# Teensylu-0_9.net
KiCad netlist of a schematic drawn in EAGLE
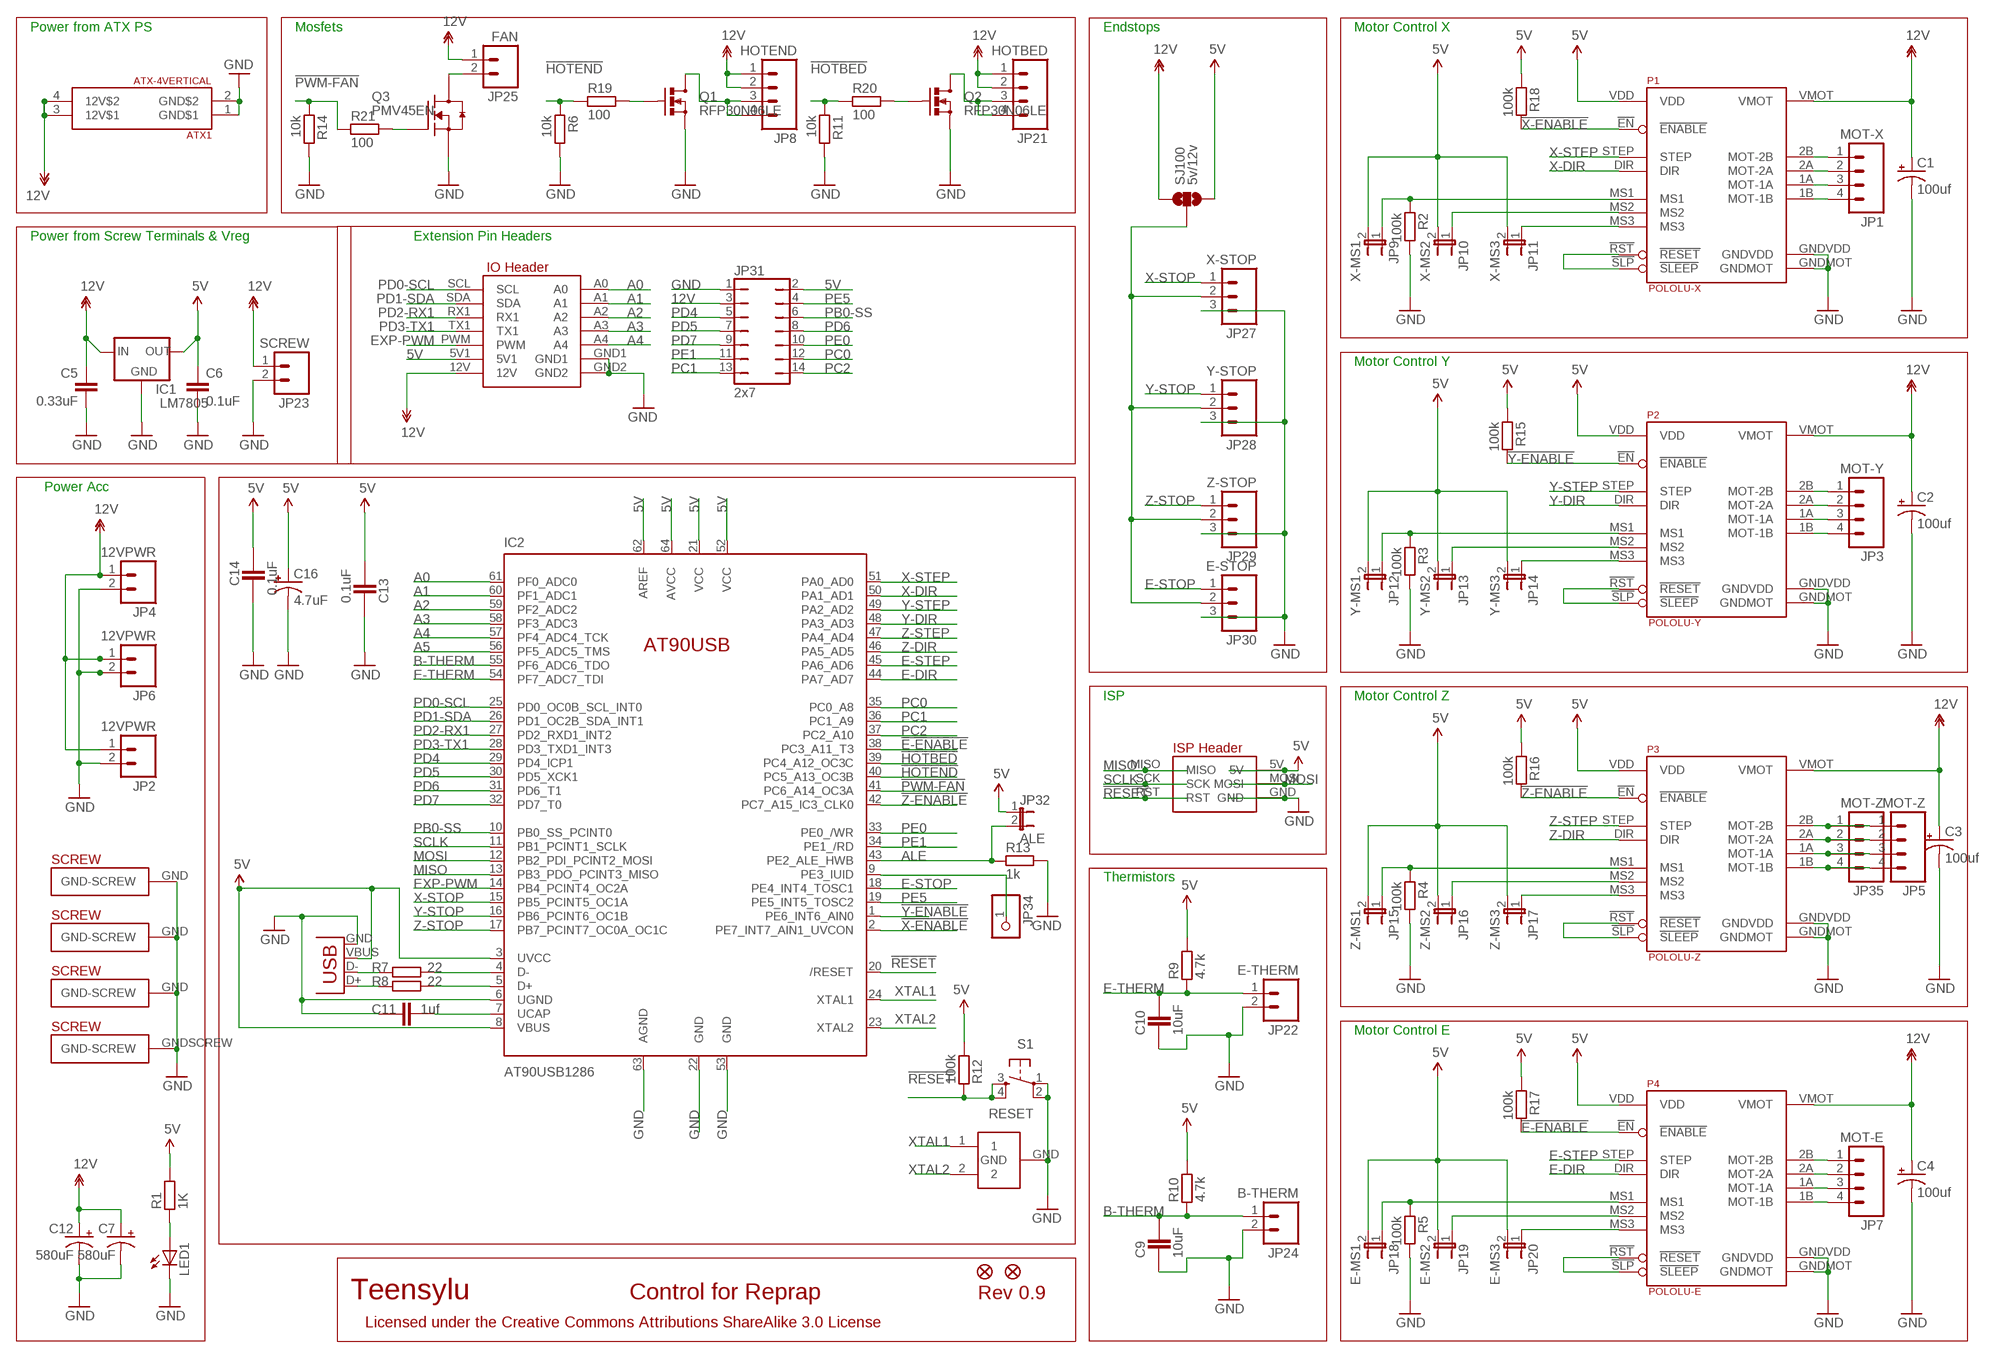
[diagram p0: schematic, sheet 1]

(export (version "E")
  (design (tool "Eeschema 10.0.6"))
  (components
    (comp (ref "ATX1")
      (value "ATX-4VERTICAL")
      (footprint "eagle-import:MINIFITJR-4-VERTICAL")
      (libsource (lib "eagle-import") (part "ATX-4VERTICAL"))
    )
    (comp (ref "C1")
      (value "100uf")
      (footprint "eagle-import:CPOL-RADIAL-100UF-25V")
      (libsource (lib "eagle-import") (part "CAP_POLPTH1"))
    )
    (comp (ref "C2")
      (value "100uf")
      (footprint "eagle-import:CPOL-RADIAL-100UF-25V")
      (libsource (lib "eagle-import") (part "CAP_POLPTH1"))
    )
    (comp (ref "C3")
      (value "100uf")
      (footprint "eagle-import:CPOL-RADIAL-100UF-25V")
      (libsource (lib "eagle-import") (part "CAP_POLPTH1"))
    )
    (comp (ref "C4")
      (value "100uf")
      (footprint "eagle-import:CPOL-RADIAL-100UF-25V")
      (libsource (lib "eagle-import") (part "CAP_POLPTH1"))
    )
    (comp (ref "C5")
      (value "0.33uF")
      (footprint "eagle-import:CAP-PTH-SMALL2")
      (libsource (lib "eagle-import") (part "CAPPTH2"))
    )
    (comp (ref "C6")
      (value "0.1uF")
      (footprint "eagle-import:CAP-PTH-SMALL2")
      (libsource (lib "eagle-import") (part "CAPPTH2"))
    )
    (comp (ref "C7")
      (value "580uF")
      (footprint "eagle-import:CPOL-RADIAL-1000UF-25V")
      (libsource (lib "eagle-import") (part "CAP_POLPTH4"))
    )
    (comp (ref "C9")
      (value "10uF")
      (footprint "eagle-import:CAPC1608X92N")
      (libsource (lib "eagle-import") (part "CAPACITOR_0603"))
    )
    (comp (ref "C10")
      (value "10uF")
      (footprint "eagle-import:CAPC1608X92N")
      (libsource (lib "eagle-import") (part "CAPACITOR_0603"))
    )
    (comp (ref "C11")
      (value "1uf")
      (footprint "eagle-import:CAPC1608X92N")
      (libsource (lib "eagle-import") (part "CAPACITOR_0603"))
    )
    (comp (ref "C12")
      (value "580uF")
      (footprint "eagle-import:CPOL-RADIAL-1000UF-25V")
      (libsource (lib "eagle-import") (part "CAP_POLPTH4"))
    )
    (comp (ref "C13")
      (value "0.1uF")
      (footprint "eagle-import:CAPC1608X92N")
      (libsource (lib "eagle-import") (part "CAPACITOR_0603"))
    )
    (comp (ref "C14")
      (value "0.1uF")
      (footprint "eagle-import:CAPC1608X92N")
      (libsource (lib "eagle-import") (part "CAPACITOR_0603"))
    )
    (comp (ref "C16")
      (value "4.7uF")
      (footprint "eagle-import:CPOL-RADIAL-10UF-25V")
      (libsource (lib "eagle-import") (part "CAP_POLPTH2"))
    )
    (comp (ref "IC1")
      (value "LM7805")
      (footprint "eagle-import:78XXL-CUSTOM")
      (libsource (lib "eagle-import") (part "V_REG_78XX"))
    )
    (comp (ref "IC2")
      (value "AT90USB1286")
      (footprint "eagle-import:TQFP64-2")
      (libsource (lib "eagle-import") (part "AT90USB"))
    )
    (comp (ref "J1")
      (value "USB")
      (footprint "eagle-import:USB-B-PTH")
      (libsource (lib "eagle-import") (part "USBPTH"))
    )
    (comp (ref "JP1")
      (value "MOT-X")
      (footprint "eagle-import:MOLEX-1X4")
      (libsource (lib "eagle-import") (part "M04POLAR"))
    )
    (comp (ref "JP2")
      (value "12VPWR")
      (footprint "eagle-import:MOLEX-1X2")
      (libsource (lib "eagle-import") (part "M02POLAR"))
    )
    (comp (ref "JP3")
      (value "MOT-Y")
      (footprint "eagle-import:MOLEX-1X4")
      (libsource (lib "eagle-import") (part "M04POLAR"))
    )
    (comp (ref "JP4")
      (value "12VPWR")
      (footprint "eagle-import:MOLEX-1X2")
      (libsource (lib "eagle-import") (part "M02POLAR"))
    )
    (comp (ref "JP5")
      (value "MOT-Z")
      (footprint "eagle-import:MOLEX-1X4")
      (libsource (lib "eagle-import") (part "M04POLAR"))
    )
    (comp (ref "JP6")
      (value "12VPWR")
      (footprint "eagle-import:MOLEX-1X2")
      (libsource (lib "eagle-import") (part "M02POLAR"))
    )
    (comp (ref "JP7")
      (value "MOT-E")
      (footprint "eagle-import:MOLEX-1X4")
      (libsource (lib "eagle-import") (part "M04POLAR"))
    )
    (comp (ref "JP8")
      (value "HOTEND")
      (footprint "eagle-import:MOLEX-1X4")
      (libsource (lib "eagle-import") (part "M04POLAR"))
    )
    (comp (ref "JP9")
      (value "X-MS1")
      (footprint "eagle-import:1X02")
      (libsource (lib "eagle-import") (part "JUMPER-2PTH"))
    )
    (comp (ref "JP10")
      (value "X-MS2")
      (footprint "eagle-import:1X02")
      (libsource (lib "eagle-import") (part "JUMPER-2PTH"))
    )
    (comp (ref "JP11")
      (value "X-MS3")
      (footprint "eagle-import:1X02")
      (libsource (lib "eagle-import") (part "JUMPER-2PTH"))
    )
    (comp (ref "JP12")
      (value "Y-MS1")
      (footprint "eagle-import:1X02")
      (libsource (lib "eagle-import") (part "JUMPER-2PTH"))
    )
    (comp (ref "JP13")
      (value "Y-MS2")
      (footprint "eagle-import:1X02")
      (libsource (lib "eagle-import") (part "JUMPER-2PTH"))
    )
    (comp (ref "JP14")
      (value "Y-MS3")
      (footprint "eagle-import:1X02")
      (libsource (lib "eagle-import") (part "JUMPER-2PTH"))
    )
    (comp (ref "JP15")
      (value "Z-MS1")
      (footprint "eagle-import:1X02")
      (libsource (lib "eagle-import") (part "JUMPER-2PTH"))
    )
    (comp (ref "JP16")
      (value "Z-MS2")
      (footprint "eagle-import:1X02")
      (libsource (lib "eagle-import") (part "JUMPER-2PTH"))
    )
    (comp (ref "JP17")
      (value "Z-MS3")
      (footprint "eagle-import:1X02")
      (libsource (lib "eagle-import") (part "JUMPER-2PTH"))
    )
    (comp (ref "JP18")
      (value "E-MS1")
      (footprint "eagle-import:1X02")
      (libsource (lib "eagle-import") (part "JUMPER-2PTH"))
    )
    (comp (ref "JP19")
      (value "E-MS2")
      (footprint "eagle-import:1X02")
      (libsource (lib "eagle-import") (part "JUMPER-2PTH"))
    )
    (comp (ref "JP20")
      (value "E-MS3")
      (footprint "eagle-import:1X02")
      (libsource (lib "eagle-import") (part "JUMPER-2PTH"))
    )
    (comp (ref "JP21")
      (value "HOTBED")
      (footprint "eagle-import:MOLEX-1X4")
      (libsource (lib "eagle-import") (part "M04POLAR"))
    )
    (comp (ref "JP22")
      (value "E-THERM")
      (footprint "eagle-import:1X02")
      (libsource (lib "eagle-import") (part "M02PTH"))
    )
    (comp (ref "JP23")
      (value "SCREW")
      (footprint "eagle-import:SCREWTERMINAL-5MM-2")
      (libsource (lib "eagle-import") (part "M025MM"))
    )
    (comp (ref "JP24")
      (value "B-THERM")
      (footprint "eagle-import:1X02")
      (libsource (lib "eagle-import") (part "M02PTH"))
    )
    (comp (ref "JP25")
      (value "FAN")
      (footprint "eagle-import:1X02")
      (libsource (lib "eagle-import") (part "M02PTH"))
    )
    (comp (ref "JP26")
      (value "FIDUCIAL1X2.5")
      (footprint "eagle-import:FIDUCIAL-1X2.5")
      (libsource (lib "eagle-import") (part "FIDUCIAL1X2.5"))
    )
    (comp (ref "JP27")
      (value "X-STOP")
      (footprint "eagle-import:MOLEX-1X3")
      (libsource (lib "eagle-import") (part "M03POLAR"))
    )
    (comp (ref "JP28")
      (value "Y-STOP")
      (footprint "eagle-import:MOLEX-1X3")
      (libsource (lib "eagle-import") (part "M03POLAR"))
    )
    (comp (ref "JP29")
      (value "Z-STOP")
      (footprint "eagle-import:MOLEX-1X3")
      (libsource (lib "eagle-import") (part "M03POLAR"))
    )
    (comp (ref "JP30")
      (value "E-STOP")
      (footprint "eagle-import:MOLEX-1X3")
      (libsource (lib "eagle-import") (part "M03POLAR"))
    )
    (comp (ref "JP31")
      (value "2x7")
      (footprint "eagle-import:JP7Q")
      (libsource (lib "eagle-import") (part "JP7Q"))
    )
    (comp (ref "JP32")
      (value "ALE")
      (footprint "eagle-import:1X02")
      (libsource (lib "eagle-import") (part "JUMPER-2PTH"))
    )
    (comp (ref "JP33")
      (value "FIDUCIAL1X2.5")
      (footprint "eagle-import:FIDUCIAL-1X2.5")
      (libsource (lib "eagle-import") (part "FIDUCIAL1X2.5"))
    )
    (comp (ref "JP34")
      (value "PINHD-1X1")
      (footprint "eagle-import:1X01")
      (libsource (lib "eagle-import") (part "PINHD-1X1"))
    )
    (comp (ref "JP35")
      (value "MOT-Z")
      (footprint "eagle-import:MOLEX-1X4")
      (libsource (lib "eagle-import") (part "M04POLAR"))
    )
    (comp (ref "LED1")
      (value "LED5MM")
      (footprint "eagle-import:LED5MM")
      (libsource (lib "eagle-import") (part "LED5MM"))
    )
    (comp (ref "P1")
      (value "POLOLU-X")
      (footprint "eagle-import:POLOLU-ALLEGRO-PTH")
      (libsource (lib "eagle-import") (part "POLOLU-ALLEGRO"))
    )
    (comp (ref "P2")
      (value "POLOLU-Y")
      (footprint "eagle-import:POLOLU-ALLEGRO-PTH")
      (libsource (lib "eagle-import") (part "POLOLU-ALLEGRO"))
    )
    (comp (ref "P3")
      (value "POLOLU-Z")
      (footprint "eagle-import:POLOLU-ALLEGRO-PTH")
      (libsource (lib "eagle-import") (part "POLOLU-ALLEGRO"))
    )
    (comp (ref "P4")
      (value "POLOLU-E")
      (footprint "eagle-import:POLOLU-ALLEGRO-PTH")
      (libsource (lib "eagle-import") (part "POLOLU-ALLEGRO"))
    )
    (comp (ref "Q1")
      (value "RFP30N06LE")
      (footprint "eagle-import:TO220V")
      (libsource (lib "eagle-import") (part "MOSFET-NCHANNELPTH2"))
    )
    (comp (ref "Q2")
      (value "RFP30N06LE")
      (footprint "eagle-import:TO220V")
      (libsource (lib "eagle-import") (part "MOSFET-NCHANNELPTH2"))
    )
    (comp (ref "Q3")
      (value "PMV45EN")
      (footprint "eagle-import:SOT95P280X135-3N")
      (libsource (lib "eagle-import") (part "MOSFET-NCH_SOT-23"))
    )
    (comp (ref "R1")
      (value "1K")
      (footprint "eagle-import:RESC1608X55N")
      (libsource (lib "eagle-import") (part "RESISTOR_0603"))
    )
    (comp (ref "R2")
      (value "100k")
      (footprint "eagle-import:RESC1608X55N")
      (libsource (lib "eagle-import") (part "RESISTOR_0603"))
    )
    (comp (ref "R3")
      (value "100k")
      (footprint "eagle-import:RESC1608X55N")
      (libsource (lib "eagle-import") (part "RESISTOR_0603"))
    )
    (comp (ref "R4")
      (value "100k")
      (footprint "eagle-import:RESC1608X55N")
      (libsource (lib "eagle-import") (part "RESISTOR_0603"))
    )
    (comp (ref "R5")
      (value "100k")
      (footprint "eagle-import:RESC1608X55N")
      (libsource (lib "eagle-import") (part "RESISTOR_0603"))
    )
    (comp (ref "R6")
      (value "10k")
      (footprint "eagle-import:RESC1608X55N")
      (libsource (lib "eagle-import") (part "RESISTOR_0603"))
    )
    (comp (ref "R7")
      (value "22")
      (footprint "eagle-import:RESC1608X55N")
      (libsource (lib "eagle-import") (part "RESISTOR_0603"))
    )
    (comp (ref "R8")
      (value "22")
      (footprint "eagle-import:RESC1608X55N")
      (libsource (lib "eagle-import") (part "RESISTOR_0603"))
    )
    (comp (ref "R9")
      (value "4.7k")
      (footprint "eagle-import:RESC1608X55N")
      (libsource (lib "eagle-import") (part "RESISTOR_0603"))
    )
    (comp (ref "R10")
      (value "4.7k")
      (footprint "eagle-import:RESC1608X55N")
      (libsource (lib "eagle-import") (part "RESISTOR_0603"))
    )
    (comp (ref "R11")
      (value "10k")
      (footprint "eagle-import:RESC1608X55N")
      (libsource (lib "eagle-import") (part "RESISTOR_0603"))
    )
    (comp (ref "R12")
      (value "100k")
      (footprint "eagle-import:RESC1608X55N")
      (libsource (lib "eagle-import") (part "RESISTOR_0603"))
    )
    (comp (ref "R13")
      (value "1k")
      (footprint "eagle-import:RESC1608X55N")
      (libsource (lib "eagle-import") (part "RESISTOR_0603"))
    )
    (comp (ref "R14")
      (value "10k")
      (footprint "eagle-import:RESC1608X55N")
      (libsource (lib "eagle-import") (part "RESISTOR_0603"))
    )
    (comp (ref "R15")
      (value "100k")
      (footprint "eagle-import:RESC1608X55N")
      (libsource (lib "eagle-import") (part "RESISTOR_0603"))
    )
    (comp (ref "R16")
      (value "100k")
      (footprint "eagle-import:RESC1608X55N")
      (libsource (lib "eagle-import") (part "RESISTOR_0603"))
    )
    (comp (ref "R17")
      (value "100k")
      (footprint "eagle-import:RESC1608X55N")
      (libsource (lib "eagle-import") (part "RESISTOR_0603"))
    )
    (comp (ref "R18")
      (value "100k")
      (footprint "eagle-import:RESC1608X55N")
      (libsource (lib "eagle-import") (part "RESISTOR_0603"))
    )
    (comp (ref "R19")
      (value "100")
      (footprint "eagle-import:RESC1608X55N")
      (libsource (lib "eagle-import") (part "RESISTOR_0603"))
    )
    (comp (ref "R20")
      (value "100")
      (footprint "eagle-import:RESC1608X55N")
      (libsource (lib "eagle-import") (part "RESISTOR_0603"))
    )
    (comp (ref "R21")
      (value "100")
      (footprint "eagle-import:RESC1608X55N")
      (libsource (lib "eagle-import") (part "RESISTOR_0603"))
    )
    (comp (ref "S1")
      (value "RESET")
      (footprint "eagle-import:TACTILE-PTH")
      (libsource (lib "eagle-import") (part "TAC_SWITCHPTH"))
    )
    (comp (ref "SJ100")
      (value "5v/12v")
      (footprint "eagle-import:SJ_2W")
      (libsource (lib "eagle-import") (part "SOLDERJUMPER_2WAYW"))
    )
    (comp (ref "U$17")
      (value "PLATED-SCREW")
      (footprint "eagle-import:PLATEDSCREW")
      (libsource (lib "eagle-import") (part "PLATED-SCREW"))
    )
    (comp (ref "U$24")
      (value "PLATED-SCREW")
      (footprint "eagle-import:PLATEDSCREW")
      (libsource (lib "eagle-import") (part "PLATED-SCREW"))
    )
    (comp (ref "U$34")
      (value "IO_HEADERS_SCREW")
      (footprint "eagle-import:IO_HEADER-PLATEDSCREW")
      (libsource (lib "eagle-import") (part "IO_HEADERS_SCREW"))
    )
    (comp (ref "U$37")
      (value "PLATED-SCREW")
      (footprint "eagle-import:PLATEDSCREW")
      (libsource (lib "eagle-import") (part "PLATED-SCREW"))
    )
    (comp (ref "XTAL")
      (value "KYOCERA_PQRC_TYPE_S_RESONATOR")
      (footprint "eagle-import:AVX_3.2X1.3_RESONATOR")
      (libsource (lib "eagle-import") (part "KYOCERA_PQRC_TYPE_S_RESONATOR"))
    )
  )
  (nets
    (net (code "1") (name "/A0") (class "Default")
      (node (ref "IC2") (pin "61") (pinfunction "PF0_ADC0_61") (pintype "bidirectional"))
      (node (ref "U$34") (pin "A0") (pinfunction "A0_A0") (pintype "bidirectional"))
    )
    (net (code "2") (name "/A1") (class "Default")
      (node (ref "IC2") (pin "60") (pinfunction "PF1_ADC1_60") (pintype "bidirectional"))
      (node (ref "U$34") (pin "A1") (pinfunction "A1_A1") (pintype "bidirectional"))
    )
    (net (code "3") (name "/A2") (class "Default")
      (node (ref "IC2") (pin "59") (pinfunction "PF2_ADC2_59") (pintype "bidirectional"))
      (node (ref "U$34") (pin "A2") (pinfunction "A2_A2") (pintype "bidirectional"))
    )
    (net (code "4") (name "/A3") (class "Default")
      (node (ref "IC2") (pin "58") (pinfunction "PF3_ADC3_58") (pintype "bidirectional"))
      (node (ref "U$34") (pin "A3") (pinfunction "A3_A3") (pintype "bidirectional"))
    )
    (net (code "5") (name "/A4") (class "Default")
      (node (ref "IC2") (pin "57") (pinfunction "PF4_ADC4_TCK_57") (pintype "bidirectional"))
      (node (ref "U$34") (pin "A4") (pinfunction "A4_A4") (pintype "bidirectional"))
    )
    (net (code "6") (name "/A5") (class "Default")
      (node (ref "IC2") (pin "56") (pinfunction "PF5_ADC5_TMS_56") (pintype "bidirectional"))
    )
    (net (code "7") (name "/ALE") (class "Default")
      (node (ref "IC2") (pin "43") (pinfunction "PE2_ALE_HWB_43") (pintype "bidirectional"))
      (node (ref "JP32") (pin "2") (pinfunction "2_2") (pintype "passive"))
      (node (ref "R13") (pin "1") (pinfunction "1_1") (pintype "passive"))
    )
    (net (code "8") (name "/B-THERM") (class "Default")
      (node (ref "C9") (pin "2") (pinfunction "2_2") (pintype "passive"))
      (node (ref "IC2") (pin "55") (pinfunction "PF6_ADC6_TDO_55") (pintype "bidirectional"))
      (node (ref "JP24") (pin "1") (pinfunction "1_1") (pintype "passive"))
      (node (ref "R10") (pin "1") (pinfunction "1_1") (pintype "passive"))
    )
    (net (code "9") (name "/E-DIR") (class "Default")
      (node (ref "IC2") (pin "44") (pinfunction "PA7_AD7_44") (pintype "bidirectional"))
      (node (ref "P4") (pin "DIR") (pinfunction "DIR_DIR") (pintype "bidirectional"))
    )
    (net (code "10") (name "/E-STEP") (class "Default")
      (node (ref "IC2") (pin "45") (pinfunction "PA6_AD6_45") (pintype "bidirectional"))
      (node (ref "P4") (pin "STEP") (pinfunction "STEP_STEP") (pintype "bidirectional"))
    )
    (net (code "11") (name "/E-STOP") (class "Default")
      (node (ref "IC2") (pin "18") (pinfunction "PE4_INT4_TOSC1_18") (pintype "bidirectional"))
      (node (ref "JP30") (pin "1") (pinfunction "1_1") (pintype "passive"))
    )
    (net (code "12") (name "/E-THERM") (class "Default")
      (node (ref "C10") (pin "2") (pinfunction "2_2") (pintype "passive"))
      (node (ref "IC2") (pin "54") (pinfunction "PF7_ADC7_TDI_54") (pintype "bidirectional"))
      (node (ref "JP22") (pin "1") (pinfunction "1_1") (pintype "passive"))
      (node (ref "R9") (pin "1") (pinfunction "1_1") (pintype "passive"))
    )
    (net (code "13") (name "/EXP-PWM") (class "Default")
      (node (ref "IC2") (pin "14") (pinfunction "PB4_PCINT4_OC2A_14") (pintype "bidirectional"))
      (node (ref "U$34") (pin "PWM") (pinfunction "PWM_PWM") (pintype "bidirectional"))
    )
    (net (code "14") (name "/MISO") (class "Default")
      (node (ref "IC2") (pin "13") (pinfunction "PB3_PDO_PCINT3_MISO_13") (pintype "bidirectional"))
      (node (ref "U$34") (pin "MISO") (pinfunction "MISO_MISO") (pintype "bidirectional"))
    )
    (net (code "15") (name "/MOSI") (class "Default")
      (node (ref "IC2") (pin "12") (pinfunction "PB2_PDI_PCINT2_MOSI_12") (pintype "bidirectional"))
      (node (ref "U$34") (pin "MOSI") (pinfunction "MOSI_MOSI") (pintype "bidirectional"))
    )
    (net (code "16") (name "/PB0-SS") (class "Default")
      (node (ref "IC2") (pin "10") (pinfunction "PB0_SS_PCINT0_10") (pintype "bidirectional"))
      (node (ref "JP31") (pin "6") (pinfunction "6_6") (pintype "passive"))
    )
    (net (code "17") (name "/PC0") (class "Default")
      (node (ref "IC2") (pin "35") (pinfunction "PC0_A8_35") (pintype "bidirectional"))
      (node (ref "JP31") (pin "12") (pinfunction "12_12") (pintype "passive"))
    )
    (net (code "18") (name "/PC1") (class "Default")
      (node (ref "IC2") (pin "36") (pinfunction "PC1_A9_36") (pintype "bidirectional"))
      (node (ref "JP31") (pin "13") (pinfunction "13_13") (pintype "passive"))
    )
    (net (code "19") (name "/PC2") (class "Default")
      (node (ref "IC2") (pin "37") (pinfunction "PC2_A10_37") (pintype "bidirectional"))
      (node (ref "JP31") (pin "14") (pinfunction "14_14") (pintype "passive"))
    )
    (net (code "20") (name "/PD0-SCL") (class "Default")
      (node (ref "IC2") (pin "25") (pinfunction "PD0_OC0B_SCL_INT0_25") (pintype "bidirectional"))
      (node (ref "U$34") (pin "SCL") (pinfunction "SCL_SCL") (pintype "bidirectional"))
    )
    (net (code "21") (name "/PD1-SDA") (class "Default")
      (node (ref "IC2") (pin "26") (pinfunction "PD1_OC2B_SDA_INT1_26") (pintype "bidirectional"))
      (node (ref "U$34") (pin "SDA") (pinfunction "SDA_SDA") (pintype "bidirectional"))
    )
    (net (code "22") (name "/PD2-RX1") (class "Default")
      (node (ref "IC2") (pin "27") (pinfunction "PD2_RXD1_INT2_27") (pintype "bidirectional"))
      (node (ref "U$34") (pin "RX1") (pinfunction "RX1_RX1") (pintype "bidirectional"))
    )
    (net (code "23") (name "/PD3-TX1") (class "Default")
      (node (ref "IC2") (pin "28") (pinfunction "PD3_TXD1_INT3_28") (pintype "bidirectional"))
      (node (ref "U$34") (pin "TX1") (pinfunction "TX1_TX1") (pintype "bidirectional"))
    )
    (net (code "24") (name "/PD4") (class "Default")
      (node (ref "IC2") (pin "29") (pinfunction "PD4_ICP1_29") (pintype "bidirectional"))
      (node (ref "JP31") (pin "5") (pinfunction "5_5") (pintype "passive"))
    )
    (net (code "25") (name "/PD5") (class "Default")
      (node (ref "IC2") (pin "30") (pinfunction "PD5_XCK1_30") (pintype "bidirectional"))
      (node (ref "JP31") (pin "7") (pinfunction "7_7") (pintype "passive"))
    )
    (net (code "26") (name "/PD6") (class "Default")
      (node (ref "IC2") (pin "31") (pinfunction "PD6_T1_31") (pintype "bidirectional"))
      (node (ref "JP31") (pin "8") (pinfunction "8_8") (pintype "passive"))
    )
    (net (code "27") (name "/PD7") (class "Default")
      (node (ref "IC2") (pin "32") (pinfunction "PD7_T0_32") (pintype "bidirectional"))
      (node (ref "JP31") (pin "9") (pinfunction "9_9") (pintype "passive"))
    )
    (net (code "28") (name "/PE0") (class "Default")
      (node (ref "IC2") (pin "33") (pinfunction "PE0_/WR_33") (pintype "bidirectional"))
      (node (ref "JP31") (pin "10") (pinfunction "10_10") (pintype "passive"))
    )
    (net (code "29") (name "/PE1") (class "Default")
      (node (ref "IC2") (pin "34") (pinfunction "PE1_/RD_34") (pintype "bidirectional"))
      (node (ref "JP31") (pin "11") (pinfunction "11_11") (pintype "passive"))
    )
    (net (code "30") (name "/PE5") (class "Default")
      (node (ref "IC2") (pin "19") (pinfunction "PE5_INT5_TOSC2_19") (pintype "bidirectional"))
      (node (ref "JP31") (pin "4") (pinfunction "4_4") (pintype "passive"))
    )
    (net (code "31") (name "/SCLK") (class "Default")
      (node (ref "IC2") (pin "11") (pinfunction "PB1_PCINT1_SCLK_11") (pintype "bidirectional"))
      (node (ref "U$34") (pin "SCK") (pinfunction "SCK_SCK") (pintype "bidirectional"))
    )
    (net (code "32") (name "/X-DIR") (class "Default")
      (node (ref "IC2") (pin "50") (pinfunction "PA1_AD1_50") (pintype "bidirectional"))
      (node (ref "P1") (pin "DIR") (pinfunction "DIR_DIR") (pintype "bidirectional"))
    )
    (net (code "33") (name "/X-STEP") (class "Default")
      (node (ref "IC2") (pin "51") (pinfunction "PA0_AD0_51") (pintype "bidirectional"))
      (node (ref "P1") (pin "STEP") (pinfunction "STEP_STEP") (pintype "bidirectional"))
    )
    (net (code "34") (name "/X-STOP") (class "Default")
      (node (ref "IC2") (pin "15") (pinfunction "PB5_PCINT5_OC1A_15") (pintype "bidirectional"))
      (node (ref "JP27") (pin "1") (pinfunction "1_1") (pintype "passive"))
    )
    (net (code "35") (name "/XTAL1") (class "Default")
      (node (ref "IC2") (pin "24") (pinfunction "XTAL1_24") (pintype "passive"))
      (node (ref "XTAL") (pin "1") (pinfunction "1_1") (pintype "bidirectional"))
    )
    (net (code "36") (name "/XTAL2") (class "Default")
      (node (ref "IC2") (pin "23") (pinfunction "XTAL2_23") (pintype "passive"))
      (node (ref "XTAL") (pin "2") (pinfunction "2_2") (pintype "bidirectional"))
    )
    (net (code "37") (name "/Y-DIR") (class "Default")
      (node (ref "IC2") (pin "48") (pinfunction "PA3_AD3_48") (pintype "bidirectional"))
      (node (ref "P2") (pin "DIR") (pinfunction "DIR_DIR") (pintype "bidirectional"))
    )
    (net (code "38") (name "/Y-STEP") (class "Default")
      (node (ref "IC2") (pin "49") (pinfunction "PA2_AD2_49") (pintype "bidirectional"))
      (node (ref "P2") (pin "STEP") (pinfunction "STEP_STEP") (pintype "bidirectional"))
    )
    (net (code "39") (name "/Y-STOP") (class "Default")
      (node (ref "IC2") (pin "16") (pinfunction "PB6_PCINT6_OC1B_16") (pintype "bidirectional"))
      (node (ref "JP28") (pin "1") (pinfunction "1_1") (pintype "passive"))
    )
    (net (code "40") (name "/Z-DIR") (class "Default")
      (node (ref "IC2") (pin "46") (pinfunction "PA5_AD5_46") (pintype "bidirectional"))
      (node (ref "P3") (pin "DIR") (pinfunction "DIR_DIR") (pintype "bidirectional"))
    )
    (net (code "41") (name "/Z-STEP") (class "Default")
      (node (ref "IC2") (pin "47") (pinfunction "PA4_AD4_47") (pintype "bidirectional"))
      (node (ref "P3") (pin "STEP") (pinfunction "STEP_STEP") (pintype "bidirectional"))
    )
    (net (code "42") (name "/Z-STOP") (class "Default")
      (node (ref "IC2") (pin "17") (pinfunction "PB7_PCINT7_OC0A_OC1C_17") (pintype "bidirectional"))
      (node (ref "JP29") (pin "1") (pinfunction "1_1") (pintype "passive"))
    )
    (net (code "43") (name "/~{E-ENABLE}") (class "Default")
      (node (ref "IC2") (pin "38") (pinfunction "PC3_A11_T3_38") (pintype "bidirectional"))
      (node (ref "P4") (pin "!EN") (pinfunction "~{ENABLE}_!EN") (pintype "input"))
      (node (ref "R17") (pin "2") (pinfunction "2_2") (pintype "passive"))
    )
    (net (code "44") (name "/~{HOTBED}") (class "Default")
      (node (ref "IC2") (pin "39") (pinfunction "PC4_A12_OC3C_39") (pintype "bidirectional"))
      (node (ref "R11") (pin "1") (pinfunction "1_1") (pintype "passive"))
      (node (ref "R20") (pin "1") (pinfunction "1_1") (pintype "passive"))
    )
    (net (code "45") (name "/~{HOTEND}") (class "Default")
      (node (ref "IC2") (pin "40") (pinfunction "PC5_A13_OC3B_40") (pintype "bidirectional"))
      (node (ref "R19") (pin "1") (pinfunction "1_1") (pintype "passive"))
      (node (ref "R6") (pin "1") (pinfunction "1_1") (pintype "passive"))
    )
    (net (code "46") (name "/~{PWM-FAN}") (class "Default")
      (node (ref "IC2") (pin "41") (pinfunction "PC6_A14_OC3A_41") (pintype "bidirectional"))
      (node (ref "R14") (pin "1") (pinfunction "1_1") (pintype "passive"))
      (node (ref "R21") (pin "1") (pinfunction "1_1") (pintype "passive"))
    )
    (net (code "47") (name "/~{RESET}") (class "Default")
      (node (ref "IC2") (pin "20") (pinfunction "/RESET_20") (pintype "bidirectional"))
      (node (ref "R12") (pin "1") (pinfunction "1_1") (pintype "passive"))
      (node (ref "S1") (pin "3") (pinfunction "3_3") (pintype "passive"))
      (node (ref "S1") (pin "4") (pinfunction "4_4") (pintype "passive"))
      (node (ref "U$34") (pin "RST") (pinfunction "RST_RST") (pintype "bidirectional"))
    )
    (net (code "48") (name "/~{X-ENABLE}") (class "Default")
      (node (ref "IC2") (pin "2") (pinfunction "PE7_INT7_AIN1_UVCON_2") (pintype "bidirectional"))
      (node (ref "P1") (pin "!EN") (pinfunction "~{ENABLE}_!EN") (pintype "input"))
      (node (ref "R18") (pin "2") (pinfunction "2_2") (pintype "passive"))
    )
    (net (code "49") (name "/~{Y-ENABLE}") (class "Default")
      (node (ref "IC2") (pin "1") (pinfunction "PE6_INT6_AIN0_1") (pintype "bidirectional"))
      (node (ref "P2") (pin "!EN") (pinfunction "~{ENABLE}_!EN") (pintype "input"))
      (node (ref "R15") (pin "2") (pinfunction "2_2") (pintype "passive"))
    )
    (net (code "50") (name "/~{Z-ENABLE}") (class "Default")
      (node (ref "IC2") (pin "42") (pinfunction "PC7_A15_IC3_CLK0_42") (pintype "bidirectional"))
      (node (ref "P3") (pin "!EN") (pinfunction "~{ENABLE}_!EN") (pintype "input"))
      (node (ref "R16") (pin "2") (pinfunction "2_2") (pintype "passive"))
    )
    (net (code "51") (name "5V") (class "Default")
      (node (ref "C13") (pin "2") (pinfunction "2_2") (pintype "passive"))
      (node (ref "C14") (pin "1") (pinfunction "1_1") (pintype "passive"))
      (node (ref "C16") (pin "1") (pinfunction "+_1") (pintype "passive"))
      (node (ref "C6") (pin "1") (pinfunction "1_1") (pintype "passive"))
      (node (ref "IC1") (pin "OUT") (pinfunction "OUT_OUT") (pintype "output"))
      (node (ref "IC2") (pin "21") (pinfunction "VCC_21") (pintype "power_in"))
      (node (ref "IC2") (pin "3") (pinfunction "UVCC_3") (pintype "power_in"))
      (node (ref "IC2") (pin "52") (pinfunction "VCC_52") (pintype "power_in"))
      (node (ref "IC2") (pin "62") (pinfunction "AREF_62") (pintype "power_in"))
      (node (ref "IC2") (pin "64") (pinfunction "AVCC_64") (pintype "power_in"))
      (node (ref "IC2") (pin "8") (pinfunction "VBUS_8") (pintype "bidirectional"))
      (node (ref "J1") (pin "VBUS") (pinfunction "VBUS_VBUS") (pintype "bidirectional"))
      (node (ref "JP10") (pin "2") (pinfunction "2_2") (pintype "passive"))
      (node (ref "JP11") (pin "2") (pinfunction "2_2") (pintype "passive"))
      (node (ref "JP12") (pin "2") (pinfunction "2_2") (pintype "passive"))
      (node (ref "JP13") (pin "2") (pinfunction "2_2") (pintype "passive"))
      (node (ref "JP14") (pin "2") (pinfunction "2_2") (pintype "passive"))
      (node (ref "JP15") (pin "2") (pinfunction "2_2") (pintype "passive"))
      (node (ref "JP16") (pin "2") (pinfunction "2_2") (pintype "passive"))
      (node (ref "JP17") (pin "2") (pinfunction "2_2") (pintype "passive"))
      (node (ref "JP18") (pin "2") (pinfunction "2_2") (pintype "passive"))
      (node (ref "JP19") (pin "2") (pinfunction "2_2") (pintype "passive"))
      (node (ref "JP20") (pin "2") (pinfunction "2_2") (pintype "passive"))
      (node (ref "JP31") (pin "2") (pinfunction "2_2") (pintype "passive"))
      (node (ref "JP32") (pin "1") (pinfunction "1_1") (pintype "passive"))
      (node (ref "JP9") (pin "2") (pinfunction "2_2") (pintype "passive"))
      (node (ref "P1") (pin "VDD") (pinfunction "VDD_VDD") (pintype "power_in"))
      (node (ref "P2") (pin "VDD") (pinfunction "VDD_VDD") (pintype "power_in"))
      (node (ref "P3") (pin "VDD") (pinfunction "VDD_VDD") (pintype "power_in"))
      (node (ref "P4") (pin "VDD") (pinfunction "VDD_VDD") (pintype "power_in"))
      (node (ref "R1") (pin "2") (pinfunction "2_2") (pintype "passive"))
      (node (ref "R10") (pin "2") (pinfunction "2_2") (pintype "passive"))
      (node (ref "R12") (pin "2") (pinfunction "2_2") (pintype "passive"))
      (node (ref "R15") (pin "1") (pinfunction "1_1") (pintype "passive"))
      (node (ref "R16") (pin "1") (pinfunction "1_1") (pintype "passive"))
      (node (ref "R17") (pin "1") (pinfunction "1_1") (pintype "passive"))
      (node (ref "R18") (pin "1") (pinfunction "1_1") (pintype "passive"))
      (node (ref "R9") (pin "2") (pinfunction "2_2") (pintype "passive"))
      (node (ref "SJ100") (pin "3") (pinfunction "3_3") (pintype "passive"))
      (node (ref "U$34") (pin "5V") (pinfunction "5V_5V") (pintype "bidirectional"))
      (node (ref "U$34") (pin "5V1") (pinfunction "5V1_5V1") (pintype "bidirectional"))
    )
    (net (code "52") (name "12V") (class "Default")
      (node (ref "ATX1") (pin "3") (pinfunction "12V$1_3") (pintype "power_in"))
      (node (ref "ATX1") (pin "4") (pinfunction "12V$2_4") (pintype "power_in"))
      (node (ref "C1") (pin "1") (pinfunction "+_1") (pintype "passive"))
      (node (ref "C12") (pin "1") (pinfunction "+_1") (pintype "passive"))
      (node (ref "C2") (pin "1") (pinfunction "+_1") (pintype "passive"))
      (node (ref "C3") (pin "1") (pinfunction "+_1") (pintype "passive"))
      (node (ref "C4") (pin "1") (pinfunction "+_1") (pintype "passive"))
      (node (ref "C5") (pin "1") (pinfunction "1_1") (pintype "passive"))
      (node (ref "C7") (pin "1") (pinfunction "+_1") (pintype "passive"))
      (node (ref "IC1") (pin "IN") (pinfunction "IN_IN") (pintype "input"))
      (node (ref "JP2") (pin "1") (pinfunction "1_1") (pintype "passive"))
      (node (ref "JP21") (pin "1") (pinfunction "1_1") (pintype "passive"))
      (node (ref "JP21") (pin "2") (pinfunction "2_2") (pintype "passive"))
      (node (ref "JP23") (pin "1") (pinfunction "1_1") (pintype "passive"))
      (node (ref "JP25") (pin "1") (pinfunction "1_1") (pintype "passive"))
      (node (ref "JP31") (pin "3") (pinfunction "3_3") (pintype "passive"))
      (node (ref "JP4") (pin "1") (pinfunction "1_1") (pintype "passive"))
      (node (ref "JP6") (pin "1") (pinfunction "1_1") (pintype "passive"))
      (node (ref "JP8") (pin "1") (pinfunction "1_1") (pintype "passive"))
      (node (ref "JP8") (pin "2") (pinfunction "2_2") (pintype "passive"))
      (node (ref "P1") (pin "VMOT") (pinfunction "VMOT_VMOT") (pintype "power_in"))
      (node (ref "P2") (pin "VMOT") (pinfunction "VMOT_VMOT") (pintype "power_in"))
      (node (ref "P3") (pin "VMOT") (pinfunction "VMOT_VMOT") (pintype "power_in"))
      (node (ref "P4") (pin "VMOT") (pinfunction "VMOT_VMOT") (pintype "power_in"))
      (node (ref "SJ100") (pin "1") (pinfunction "1_1") (pintype "passive"))
      (node (ref "U$34") (pin "12V") (pinfunction "12V_12V") (pintype "bidirectional"))
    )
    (net (code "53") (name "GND") (class "Default")
      (node (ref "ATX1") (pin "1") (pinfunction "GND$1_1") (pintype "power_in"))
      (node (ref "ATX1") (pin "2") (pinfunction "GND$2_2") (pintype "power_in"))
      (node (ref "C1") (pin "2") (pinfunction "-_2") (pintype "passive"))
      (node (ref "C10") (pin "1") (pinfunction "1_1") (pintype "passive"))
      (node (ref "C11") (pin "1") (pinfunction "1_1") (pintype "passive"))
      (node (ref "C12") (pin "2") (pinfunction "-_2") (pintype "passive"))
      (node (ref "C13") (pin "1") (pinfunction "1_1") (pintype "passive"))
      (node (ref "C14") (pin "2") (pinfunction "2_2") (pintype "passive"))
      (node (ref "C16") (pin "2") (pinfunction "-_2") (pintype "passive"))
      (node (ref "C2") (pin "2") (pinfunction "-_2") (pintype "passive"))
      (node (ref "C3") (pin "2") (pinfunction "-_2") (pintype "passive"))
      (node (ref "C4") (pin "2") (pinfunction "-_2") (pintype "passive"))
      (node (ref "C5") (pin "2") (pinfunction "2_2") (pintype "passive"))
      (node (ref "C6") (pin "2") (pinfunction "2_2") (pintype "passive"))
      (node (ref "C7") (pin "2") (pinfunction "-_2") (pintype "passive"))
      (node (ref "C9") (pin "1") (pinfunction "1_1") (pintype "passive"))
      (node (ref "IC1") (pin "GND") (pinfunction "GND_GND") (pintype "input"))
      (node (ref "IC2") (pin "22") (pinfunction "GND_22") (pintype "power_in"))
      (node (ref "IC2") (pin "53") (pinfunction "GND_53") (pintype "power_in"))
      (node (ref "IC2") (pin "6") (pinfunction "UGND_6") (pintype "power_in"))
      (node (ref "IC2") (pin "63") (pinfunction "AGND_63") (pintype "power_in"))
      (node (ref "J1") (pin "GND") (pinfunction "GND_GND") (pintype "bidirectional"))
      (node (ref "JP2") (pin "2") (pinfunction "2_2") (pintype "passive"))
      (node (ref "JP22") (pin "2") (pinfunction "2_2") (pintype "passive"))
      (node (ref "JP23") (pin "2") (pinfunction "2_2") (pintype "passive"))
      (node (ref "JP24") (pin "2") (pinfunction "2_2") (pintype "passive"))
      (node (ref "JP27") (pin "3") (pinfunction "3_3") (pintype "passive"))
      (node (ref "JP28") (pin "3") (pinfunction "3_3") (pintype "passive"))
      (node (ref "JP29") (pin "3") (pinfunction "3_3") (pintype "passive"))
      (node (ref "JP30") (pin "3") (pinfunction "3_3") (pintype "passive"))
      (node (ref "JP31") (pin "1") (pinfunction "1_1") (pintype "passive"))
      (node (ref "JP4") (pin "2") (pinfunction "2_2") (pintype "passive"))
      (node (ref "JP6") (pin "2") (pinfunction "2_2") (pintype "passive"))
      (node (ref "LED1") (pin "K") (pinfunction "C_K") (pintype "passive"))
      (node (ref "P1") (pin "GNDMOT") (pinfunction "GNDMOT_GNDMOT") (pintype "power_in"))
      (node (ref "P1") (pin "GNDVDD") (pinfunction "GNDVDD_GNDVDD") (pintype "power_in"))
      (node (ref "P2") (pin "GNDMOT") (pinfunction "GNDMOT_GNDMOT") (pintype "power_in"))
      (node (ref "P2") (pin "GNDVDD") (pinfunction "GNDVDD_GNDVDD") (pintype "power_in"))
      (node (ref "P3") (pin "GNDMOT") (pinfunction "GNDMOT_GNDMOT") (pintype "power_in"))
      (node (ref "P3") (pin "GNDVDD") (pinfunction "GNDVDD_GNDVDD") (pintype "power_in"))
      (node (ref "P4") (pin "GNDMOT") (pinfunction "GNDMOT_GNDMOT") (pintype "power_in"))
      (node (ref "P4") (pin "GNDVDD") (pinfunction "GNDVDD_GNDVDD") (pintype "power_in"))
      (node (ref "Q1") (pin "3") (pinfunction "S_3") (pintype "passive"))
      (node (ref "Q2") (pin "3") (pinfunction "S_3") (pintype "passive"))
      (node (ref "Q3") (pin "2") (pinfunction "S_2") (pintype "passive"))
      (node (ref "R11") (pin "2") (pinfunction "2_2") (pintype "passive"))
      (node (ref "R13") (pin "2") (pinfunction "2_2") (pintype "passive"))
      (node (ref "R14") (pin "2") (pinfunction "2_2") (pintype "passive"))
      (node (ref "R2") (pin "2") (pinfunction "2_2") (pintype "passive"))
      (node (ref "R3") (pin "2") (pinfunction "2_2") (pintype "passive"))
      (node (ref "R4") (pin "2") (pinfunction "2_2") (pintype "passive"))
      (node (ref "R5") (pin "2") (pinfunction "2_2") (pintype "passive"))
      (node (ref "R6") (pin "2") (pinfunction "2_2") (pintype "passive"))
      (node (ref "S1") (pin "1") (pinfunction "1_1") (pintype "passive"))
      (node (ref "S1") (pin "2") (pinfunction "2_2") (pintype "passive"))
      (node (ref "U$17") (pin "GND") (pinfunction "GND-SCREW_GND") (pintype "bidirectional"))
      (node (ref "U$24") (pin "GND") (pinfunction "GND-SCREW_GND") (pintype "bidirectional"))
      (node (ref "U$34") (pin "GND") (pinfunction "GND_GND") (pintype "bidirectional"))
      (node (ref "U$34") (pin "GND1") (pinfunction "GND1_GND1") (pintype "bidirectional"))
      (node (ref "U$34") (pin "GND2") (pinfunction "GND2_GND2") (pintype "bidirectional"))
      (node (ref "U$34") (pin "GNDSCREW") (pinfunction "GND-SCREW_GNDSCREW") (pintype "bidirectional"))
      (node (ref "U$37") (pin "GND") (pinfunction "GND-SCREW_GND") (pintype "bidirectional"))
      (node (ref "XTAL") (pin "GND") (pinfunction "GND_GND") (pintype "bidirectional"))
    )
    (net (code "54") (name "Net-(IC2-D+)") (class "Default")
      (node (ref "IC2") (pin "5") (pinfunction "D+_5") (pintype "bidirectional"))
      (node (ref "R8") (pin "2") (pinfunction "2_2") (pintype "passive"))
    )
    (net (code "55") (name "Net-(IC2-D-)") (class "Default")
      (node (ref "IC2") (pin "4") (pinfunction "D-_4") (pintype "bidirectional"))
      (node (ref "R7") (pin "2") (pinfunction "2_2") (pintype "passive"))
    )
    (net (code "56") (name "Net-(IC2-PE3_IUID)") (class "Default")
      (node (ref "IC2") (pin "9") (pinfunction "PE3_IUID_9") (pintype "bidirectional"))
      (node (ref "JP34") (pin "1") (pinfunction "1_1") (pintype "passive"))
    )
    (net (code "57") (name "Net-(IC2-UCAP)") (class "Default")
      (node (ref "C11") (pin "2") (pinfunction "2_2") (pintype "passive"))
      (node (ref "IC2") (pin "7") (pinfunction "UCAP_7") (pintype "power_in"))
    )
    (net (code "58") (name "Net-(J1-PadD+)") (class "Default")
      (node (ref "J1") (pin "D+") (pinfunction "D+_D+") (pintype "bidirectional"))
      (node (ref "R8") (pin "1") (pinfunction "1_1") (pintype "passive"))
    )
    (net (code "59") (name "Net-(J1-PadD-)") (class "Default")
      (node (ref "J1") (pin "D-") (pinfunction "D-_D-") (pintype "bidirectional"))
      (node (ref "R7") (pin "1") (pinfunction "1_1") (pintype "passive"))
    )
    (net (code "60") (name "Net-(JP9-Pad1)") (class "Default")
      (node (ref "JP9") (pin "1") (pinfunction "1_1") (pintype "passive"))
      (node (ref "P1") (pin "MS1") (pinfunction "MS1_MS1") (pintype "input"))
      (node (ref "R2") (pin "1") (pinfunction "1_1") (pintype "passive"))
    )
    (net (code "61") (name "Net-(JP10-Pad1)") (class "Default")
      (node (ref "JP10") (pin "1") (pinfunction "1_1") (pintype "passive"))
      (node (ref "P1") (pin "MS2") (pinfunction "MS2_MS2") (pintype "input"))
    )
    (net (code "62") (name "Net-(JP11-Pad1)") (class "Default")
      (node (ref "JP11") (pin "1") (pinfunction "1_1") (pintype "passive"))
      (node (ref "P1") (pin "MS3") (pinfunction "MS3_MS3") (pintype "input"))
    )
    (net (code "63") (name "Net-(JP12-Pad1)") (class "Default")
      (node (ref "JP12") (pin "1") (pinfunction "1_1") (pintype "passive"))
      (node (ref "P2") (pin "MS1") (pinfunction "MS1_MS1") (pintype "input"))
      (node (ref "R3") (pin "1") (pinfunction "1_1") (pintype "passive"))
    )
    (net (code "64") (name "Net-(JP13-Pad1)") (class "Default")
      (node (ref "JP13") (pin "1") (pinfunction "1_1") (pintype "passive"))
      (node (ref "P2") (pin "MS2") (pinfunction "MS2_MS2") (pintype "input"))
    )
    (net (code "65") (name "Net-(JP14-Pad1)") (class "Default")
      (node (ref "JP14") (pin "1") (pinfunction "1_1") (pintype "passive"))
      (node (ref "P2") (pin "MS3") (pinfunction "MS3_MS3") (pintype "input"))
    )
    (net (code "66") (name "Net-(JP15-Pad1)") (class "Default")
      (node (ref "JP15") (pin "1") (pinfunction "1_1") (pintype "passive"))
      (node (ref "P3") (pin "MS1") (pinfunction "MS1_MS1") (pintype "input"))
      (node (ref "R4") (pin "1") (pinfunction "1_1") (pintype "passive"))
    )
    (net (code "67") (name "Net-(JP16-Pad1)") (class "Default")
      (node (ref "JP16") (pin "1") (pinfunction "1_1") (pintype "passive"))
      (node (ref "P3") (pin "MS2") (pinfunction "MS2_MS2") (pintype "input"))
    )
    (net (code "68") (name "Net-(JP17-Pad1)") (class "Default")
      (node (ref "JP17") (pin "1") (pinfunction "1_1") (pintype "passive"))
      (node (ref "P3") (pin "MS3") (pinfunction "MS3_MS3") (pintype "input"))
    )
    (net (code "69") (name "Net-(JP18-Pad1)") (class "Default")
      (node (ref "JP18") (pin "1") (pinfunction "1_1") (pintype "passive"))
      (node (ref "P4") (pin "MS1") (pinfunction "MS1_MS1") (pintype "input"))
      (node (ref "R5") (pin "1") (pinfunction "1_1") (pintype "passive"))
    )
    (net (code "70") (name "Net-(JP19-Pad1)") (class "Default")
      (node (ref "JP19") (pin "1") (pinfunction "1_1") (pintype "passive"))
      (node (ref "P4") (pin "MS2") (pinfunction "MS2_MS2") (pintype "input"))
    )
    (net (code "71") (name "Net-(JP20-Pad1)") (class "Default")
      (node (ref "JP20") (pin "1") (pinfunction "1_1") (pintype "passive"))
      (node (ref "P4") (pin "MS3") (pinfunction "MS3_MS3") (pintype "input"))
    )
    (net (code "72") (name "Net-(JP27-Pad2)") (class "Default")
      (node (ref "JP27") (pin "2") (pinfunction "2_2") (pintype "passive"))
      (node (ref "JP28") (pin "2") (pinfunction "2_2") (pintype "passive"))
      (node (ref "JP29") (pin "2") (pinfunction "2_2") (pintype "passive"))
      (node (ref "JP30") (pin "2") (pinfunction "2_2") (pintype "passive"))
      (node (ref "SJ100") (pin "2") (pinfunction "2_2") (pintype "passive"))
    )
    (net (code "73") (name "Net-(LED1-PadA)") (class "Default")
      (node (ref "LED1") (pin "A") (pinfunction "A_A") (pintype "passive"))
      (node (ref "R1") (pin "1") (pinfunction "1_1") (pintype "passive"))
    )
    (net (code "74") (name "Net-(P1-MOT-1A)") (class "Default")
      (node (ref "JP1") (pin "3") (pinfunction "3_3") (pintype "passive"))
      (node (ref "P1") (pin "1A") (pinfunction "MOT-1A_1A") (pintype "power_in"))
    )
    (net (code "75") (name "Net-(P1-MOT-1B)") (class "Default")
      (node (ref "JP1") (pin "4") (pinfunction "4_4") (pintype "passive"))
      (node (ref "P1") (pin "1B") (pinfunction "MOT-1B_1B") (pintype "power_in"))
    )
    (net (code "76") (name "Net-(P1-MOT-2A)") (class "Default")
      (node (ref "JP1") (pin "2") (pinfunction "2_2") (pintype "passive"))
      (node (ref "P1") (pin "2A") (pinfunction "MOT-2A_2A") (pintype "power_in"))
    )
    (net (code "77") (name "Net-(P1-MOT-2B)") (class "Default")
      (node (ref "JP1") (pin "1") (pinfunction "1_1") (pintype "passive"))
      (node (ref "P1") (pin "2B") (pinfunction "MOT-2B_2B") (pintype "power_in"))
    )
    (net (code "78") (name "Net-(P1-~{RESET})") (class "Default")
      (node (ref "P1") (pin "!RST") (pinfunction "~{RESET}_!RST") (pintype "input"))
      (node (ref "P1") (pin "!SLP") (pinfunction "~{SLEEP}_!SLP") (pintype "input"))
    )
    (net (code "79") (name "Net-(P2-MOT-1A)") (class "Default")
      (node (ref "JP3") (pin "3") (pinfunction "3_3") (pintype "passive"))
      (node (ref "P2") (pin "1A") (pinfunction "MOT-1A_1A") (pintype "power_in"))
    )
    (net (code "80") (name "Net-(P2-MOT-1B)") (class "Default")
      (node (ref "JP3") (pin "4") (pinfunction "4_4") (pintype "passive"))
      (node (ref "P2") (pin "1B") (pinfunction "MOT-1B_1B") (pintype "power_in"))
    )
    (net (code "81") (name "Net-(P2-MOT-2A)") (class "Default")
      (node (ref "JP3") (pin "2") (pinfunction "2_2") (pintype "passive"))
      (node (ref "P2") (pin "2A") (pinfunction "MOT-2A_2A") (pintype "power_in"))
    )
    (net (code "82") (name "Net-(P2-MOT-2B)") (class "Default")
      (node (ref "JP3") (pin "1") (pinfunction "1_1") (pintype "passive"))
      (node (ref "P2") (pin "2B") (pinfunction "MOT-2B_2B") (pintype "power_in"))
    )
    (net (code "83") (name "Net-(P2-~{RESET})") (class "Default")
      (node (ref "P2") (pin "!RST") (pinfunction "~{RESET}_!RST") (pintype "input"))
      (node (ref "P2") (pin "!SLP") (pinfunction "~{SLEEP}_!SLP") (pintype "input"))
    )
    (net (code "84") (name "Net-(P3-MOT-1A)") (class "Default")
      (node (ref "JP35") (pin "3") (pinfunction "3_3") (pintype "passive"))
      (node (ref "JP5") (pin "3") (pinfunction "3_3") (pintype "passive"))
      (node (ref "P3") (pin "1A") (pinfunction "MOT-1A_1A") (pintype "power_in"))
    )
    (net (code "85") (name "Net-(P3-MOT-1B)") (class "Default")
      (node (ref "JP35") (pin "4") (pinfunction "4_4") (pintype "passive"))
      (node (ref "JP5") (pin "4") (pinfunction "4_4") (pintype "passive"))
      (node (ref "P3") (pin "1B") (pinfunction "MOT-1B_1B") (pintype "power_in"))
    )
    (net (code "86") (name "Net-(P3-MOT-2A)") (class "Default")
      (node (ref "JP35") (pin "2") (pinfunction "2_2") (pintype "passive"))
      (node (ref "JP5") (pin "2") (pinfunction "2_2") (pintype "passive"))
      (node (ref "P3") (pin "2A") (pinfunction "MOT-2A_2A") (pintype "power_in"))
    )
    (net (code "87") (name "Net-(P3-MOT-2B)") (class "Default")
      (node (ref "JP35") (pin "1") (pinfunction "1_1") (pintype "passive"))
      (node (ref "JP5") (pin "1") (pinfunction "1_1") (pintype "passive"))
      (node (ref "P3") (pin "2B") (pinfunction "MOT-2B_2B") (pintype "power_in"))
    )
    (net (code "88") (name "Net-(P3-~{RESET})") (class "Default")
      (node (ref "P3") (pin "!RST") (pinfunction "~{RESET}_!RST") (pintype "input"))
      (node (ref "P3") (pin "!SLP") (pinfunction "~{SLEEP}_!SLP") (pintype "input"))
    )
    (net (code "89") (name "Net-(P4-MOT-1A)") (class "Default")
      (node (ref "JP7") (pin "3") (pinfunction "3_3") (pintype "passive"))
      (node (ref "P4") (pin "1A") (pinfunction "MOT-1A_1A") (pintype "power_in"))
    )
    (net (code "90") (name "Net-(P4-MOT-1B)") (class "Default")
      (node (ref "JP7") (pin "4") (pinfunction "4_4") (pintype "passive"))
      (node (ref "P4") (pin "1B") (pinfunction "MOT-1B_1B") (pintype "power_in"))
    )
    (net (code "91") (name "Net-(P4-MOT-2A)") (class "Default")
      (node (ref "JP7") (pin "2") (pinfunction "2_2") (pintype "passive"))
      (node (ref "P4") (pin "2A") (pinfunction "MOT-2A_2A") (pintype "power_in"))
    )
    (net (code "92") (name "Net-(P4-MOT-2B)") (class "Default")
      (node (ref "JP7") (pin "1") (pinfunction "1_1") (pintype "passive"))
      (node (ref "P4") (pin "2B") (pinfunction "MOT-2B_2B") (pintype "power_in"))
    )
    (net (code "93") (name "Net-(P4-~{RESET})") (class "Default")
      (node (ref "P4") (pin "!RST") (pinfunction "~{RESET}_!RST") (pintype "input"))
      (node (ref "P4") (pin "!SLP") (pinfunction "~{SLEEP}_!SLP") (pintype "input"))
    )
    (net (code "94") (name "Net-(Q1-D)") (class "Default")
      (node (ref "JP8") (pin "3") (pinfunction "3_3") (pintype "passive"))
      (node (ref "JP8") (pin "4") (pinfunction "4_4") (pintype "passive"))
      (node (ref "Q1") (pin "2") (pinfunction "D_2") (pintype "passive"))
    )
    (net (code "95") (name "Net-(Q1-G)") (class "Default")
      (node (ref "Q1") (pin "1") (pinfunction "G_1") (pintype "passive"))
      (node (ref "R19") (pin "2") (pinfunction "2_2") (pintype "passive"))
    )
    (net (code "96") (name "Net-(Q2-D)") (class "Default")
      (node (ref "JP21") (pin "3") (pinfunction "3_3") (pintype "passive"))
      (node (ref "JP21") (pin "4") (pinfunction "4_4") (pintype "passive"))
      (node (ref "Q2") (pin "2") (pinfunction "D_2") (pintype "passive"))
    )
    (net (code "97") (name "Net-(Q2-G)") (class "Default")
      (node (ref "Q2") (pin "1") (pinfunction "G_1") (pintype "passive"))
      (node (ref "R20") (pin "2") (pinfunction "2_2") (pintype "passive"))
    )
    (net (code "98") (name "Net-(Q3-D)") (class "Default")
      (node (ref "JP25") (pin "2") (pinfunction "2_2") (pintype "passive"))
      (node (ref "Q3") (pin "3") (pinfunction "D_3") (pintype "passive"))
    )
    (net (code "99") (name "Net-(Q3-G)") (class "Default")
      (node (ref "Q3") (pin "1") (pinfunction "G_1") (pintype "passive"))
      (node (ref "R21") (pin "2") (pinfunction "2_2") (pintype "passive"))
    )
  )
)
